# Wah_PCB.net
KiCad netlist of a schematic drawn in Altium Designer
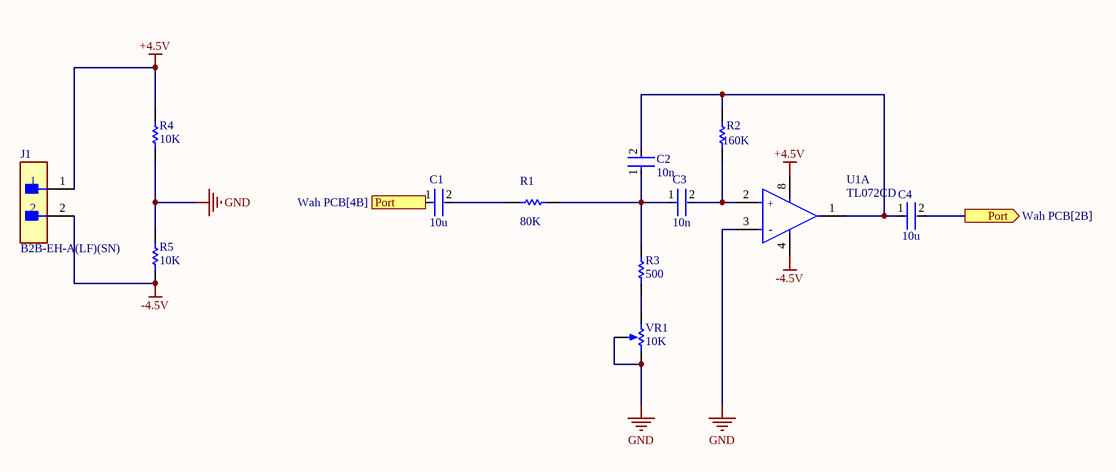
[diagram p0: Wah PCB.SchDoc]

(export (version "E")
  (design (tool "Eeschema 10.0.6"))
  (components
    (comp (ref "C1")
      (value "10u")
      (footprint "FP-F471K33Y5RP6UK5R-MFG")
      (description "CAP CER 470PF 2KV Y5R RADIAL")
      (fields (field (name "TOLERANCE") "10%") (field (name "VOLTAGE") "2kV"))
      (libsource (lib "Altium Content Vault") (part "b4654b650e69147ec39a6b967a45e02"))
    )
    (comp (ref "C2")
      (value "10n")
      (footprint "FP-F471K33Y5RP6UK5R-MFG")
      (description "CAP CER 470PF 2KV Y5R RADIAL")
      (fields (field (name "TOLERANCE") "10%") (field (name "VOLTAGE") "2kV"))
      (libsource (lib "Altium Content Vault") (part "b4654b650e69147ec39a6b967a45e02"))
    )
    (comp (ref "C3")
      (value "10n")
      (footprint "FP-F471K33Y5RP6UK5R-MFG")
      (description "CAP CER 470PF 2KV Y5R RADIAL")
      (fields (field (name "TOLERANCE") "10%") (field (name "VOLTAGE") "2kV"))
      (libsource (lib "Altium Content Vault") (part "b4654b650e69147ec39a6b967a45e02"))
    )
    (comp (ref "C4")
      (value "10u")
      (footprint "FP-F471K33Y5RP6UK5R-MFG")
      (description "CAP CER 470PF 2KV Y5R RADIAL")
      (fields (field (name "TOLERANCE") "10%") (field (name "VOLTAGE") "2kV"))
      (libsource (lib "Altium Content Vault") (part "b4654b650e69147ec39a6b967a45e02"))
    )
    (comp (ref "J1")
      (value "B2B-EH-A(LF)(SN)")
      (footprint "FP-B2B-EH-A_LF_SN-MFG")
      (description "CONN HEADER VERT 2POS 2.5MM")
      (libsource (lib "Altium Content Vault") (part "3bc925449376181038e59eaffc5286c"))
    )
    (comp (ref "R1")
      (value "80K")
      (footprint "RESA60-630X240")
      (description "Axial Resistor, 47.5 Ohm, +/- 1%, 0.25 W, -55 to 155 degC, 2-Pin THD, RoHS, Bulk")
      (libsource (lib "Altium Content Vault") (part "RES-2"))
    )
    (comp (ref "R2")
      (value "160K")
      (footprint "RESA60-630X240")
      (description "Axial Resistor, 47.5 Ohm, +/- 1%, 0.25 W, -55 to 155 degC, 2-Pin THD, RoHS, Bulk")
      (libsource (lib "Altium Content Vault") (part "RES-2"))
    )
    (comp (ref "R3")
      (value "500")
      (footprint "RESA60-630X240")
      (description "Axial Resistor, 47.5 Ohm, +/- 1%, 0.25 W, -55 to 155 degC, 2-Pin THD, RoHS, Bulk")
      (libsource (lib "Altium Content Vault") (part "RES-2"))
    )
    (comp (ref "R4")
      (value "10K")
      (footprint "RESA60-630X240")
      (description "Axial Resistor, 47.5 Ohm, +/- 1%, 0.25 W, -55 to 155 degC, 2-Pin THD, RoHS, Bulk")
      (libsource (lib "Altium Content Vault") (part "RES-2"))
    )
    (comp (ref "R5")
      (value "10K")
      (footprint "RESA60-630X240")
      (description "Axial Resistor, 47.5 Ohm, +/- 1%, 0.25 W, -55 to 155 degC, 2-Pin THD, RoHS, Bulk")
      (libsource (lib "Altium Content Vault") (part "RES-2"))
    )
    (comp (ref "U1")
      (value "TL072CD")
      (footprint "FP-SO8-IPC_C")
      (description "IC OPAMP JFET 2 CIRCUIT 8SO")
      (libsource (lib "Altium Content Vault") (part "78142e87b7ae7ad9e0533b2c6f3fb9c"))
    )
    (comp (ref "VR1")
      (value "10K")
      (footprint "BOUR-3852A-282-103AL-3_V")
      (description "Diameter Panel Control, 10 KOhm, +/- 10%, 2 W, -1 to 125 degC, 3-Pin THD, RoHS, Bulk")
      (fields (field (name "TOLERANCE") "±10%") (field (name "MANUFACTURER") "Bourns"))
      (libsource (lib "Altium Content Vault") (part "RES-POT-3"))
    )
  )
  (nets
    (net (code "1") (name "+4.5V") (class "Default")
      (node (ref "J1") (pin "1") (pinfunction "1_1") (pintype "passive"))
      (node (ref "R4") (pin "2") (pinfunction "2_2") (pintype "passive"))
      (node (ref "U1") (pin "8") (pinfunction "VCC+_8") (pintype "power_in"))
    )
    (net (code "2") (name "-4.5V") (class "Default")
      (node (ref "J1") (pin "2") (pinfunction "2_2") (pintype "passive"))
      (node (ref "R5") (pin "1") (pinfunction "1_1") (pintype "passive"))
      (node (ref "U1") (pin "4") (pinfunction "VCC-_4") (pintype "power_in"))
    )
    (net (code "4") (name "/Port") (class "Default")
      (node (ref "C1") (pin "1") (pinfunction "1_1") (pintype "passive"))
      (node (ref "C4") (pin "2") (pinfunction "2_2") (pintype "passive"))
    )
    (net (code "5") (name "GND") (class "Default")
      (node (ref "R4") (pin "1") (pinfunction "1_1") (pintype "passive"))
      (node (ref "R5") (pin "2") (pinfunction "2_2") (pintype "passive"))
      (node (ref "U1") (pin "3") (pinfunction "Non-inverting_input_1_3") (pintype "tri_state"))
      (node (ref "VR1") (pin "2") (pinfunction "S_2") (pintype "passive"))
      (node (ref "VR1") (pin "3") (pinfunction "CW_3") (pintype "passive"))
    )
    (net (code "6") (name "Net-(C1-Pad2)") (class "Default")
      (node (ref "C1") (pin "2") (pinfunction "2_2") (pintype "passive"))
      (node (ref "R1") (pin "1") (pinfunction "1_1") (pintype "passive"))
    )
    (net (code "7") (name "Net-(C2-Pad1)") (class "Default")
      (node (ref "C2") (pin "1") (pinfunction "1_1") (pintype "passive"))
      (node (ref "C3") (pin "1") (pinfunction "1_1") (pintype "passive"))
      (node (ref "R1") (pin "2") (pinfunction "2_2") (pintype "passive"))
      (node (ref "R3") (pin "2") (pinfunction "2_2") (pintype "passive"))
    )
    (net (code "8") (name "Net-(U1A-Inverting_input_1)") (class "Default")
      (node (ref "C3") (pin "2") (pinfunction "2_2") (pintype "passive"))
      (node (ref "R2") (pin "1") (pinfunction "1_1") (pintype "passive"))
      (node (ref "U1") (pin "2") (pinfunction "Inverting_input_1_2") (pintype "tri_state"))
    )
    (net (code "9") (name "Net-(U1A-Output_1)") (class "Default")
      (node (ref "C2") (pin "2") (pinfunction "2_2") (pintype "passive"))
      (node (ref "C4") (pin "1") (pinfunction "1_1") (pintype "passive"))
      (node (ref "R2") (pin "2") (pinfunction "2_2") (pintype "passive"))
      (node (ref "U1") (pin "1") (pinfunction "Output_1_1") (pintype "passive"))
    )
    (net (code "10") (name "Net-(VR1-CCW)") (class "Default")
      (node (ref "R3") (pin "1") (pinfunction "1_1") (pintype "passive"))
      (node (ref "VR1") (pin "1") (pinfunction "CCW_1") (pintype "passive"))
    )
  )
)
